# TCAN330_PINOUT.net
KiCad netlist of a schematic drawn in Altium Designer
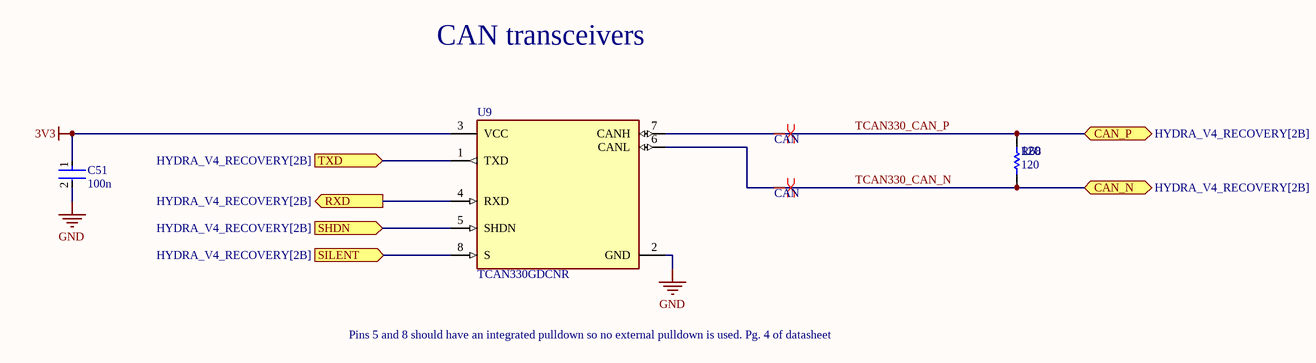
[diagram p0: TCAN330_PINOUT.SchDoc]

(export (version "E")
  (design (tool "Eeschema 10.0.6"))
  (components
    (comp (ref "C51")
      (value "100n")
      (footprint "FP-0402-L_1_0_0_05-W_0_5-IPC_A")
      (description "LARGE PADS, 0402 CAP, CHANGE COMMENT TO MATCH REAL P/N")
      (libsource (lib "Space Concordia") (part "b4654b650e69147ec39a6b967a45e02"))
    )
    (comp (ref "R68")
      (value "120")
      (footprint "R0603B")
      (description "Resistor")
      (fields (field (name "ALTIUM_VALUE") "120"))
      (libsource (lib "Space Concordia") (part "Resistor"))
    )
    (comp (ref "U9")
      (value "TCAN330GDCNR")
      (footprint "FP-DCN0008A-MFG")
      (description "IC TRANSCEIVER 1/1 SOT23-8")
      (libsource (lib "Altium Content Vault") (part "22681b49c22ad38c6a4e12e04c36c7a"))
    )
  )
  (nets
    (net (code "1") (name "/RXD") (class "Default")
      (node (ref "U9") (pin "4") (pinfunction "RXD_4") (pintype "input"))
    )
    (net (code "2") (name "/SHDN") (class "Default")
      (node (ref "U9") (pin "5") (pinfunction "SHDN_5") (pintype "input"))
    )
    (net (code "3") (name "/SILENT") (class "Default")
      (node (ref "U9") (pin "8") (pinfunction "S_8") (pintype "input"))
    )
    (net (code "4") (name "/TCAN330_CAN_N") (class "Default")
      (node (ref "R68") (pin "1") (pinfunction "1_1") (pintype "passive"))
      (node (ref "U9") (pin "6") (pinfunction "CANL_6") (pintype "bidirectional"))
    )
    (net (code "5") (name "/TCAN330_CAN_P") (class "Default")
      (node (ref "R68") (pin "2") (pinfunction "2_2") (pintype "passive"))
      (node (ref "U9") (pin "7") (pinfunction "CANH_7") (pintype "bidirectional"))
    )
    (net (code "6") (name "/TXD") (class "Default")
      (node (ref "U9") (pin "1") (pinfunction "TXD_1") (pintype "output"))
    )
    (net (code "7") (name "3V3") (class "Default")
      (node (ref "C51") (pin "1") (pinfunction "1_1") (pintype "passive"))
      (node (ref "U9") (pin "3") (pinfunction "VCC_3") (pintype "power_in"))
    )
    (net (code "8") (name "GND") (class "Default")
      (node (ref "C51") (pin "2") (pinfunction "2_2") (pintype "passive"))
      (node (ref "U9") (pin "2") (pinfunction "GND_2") (pintype "power_in"))
    )
  )
)
